# xmas_tree_pcb_A.net
KiCad netlist of a schematic drawn in EAGLE
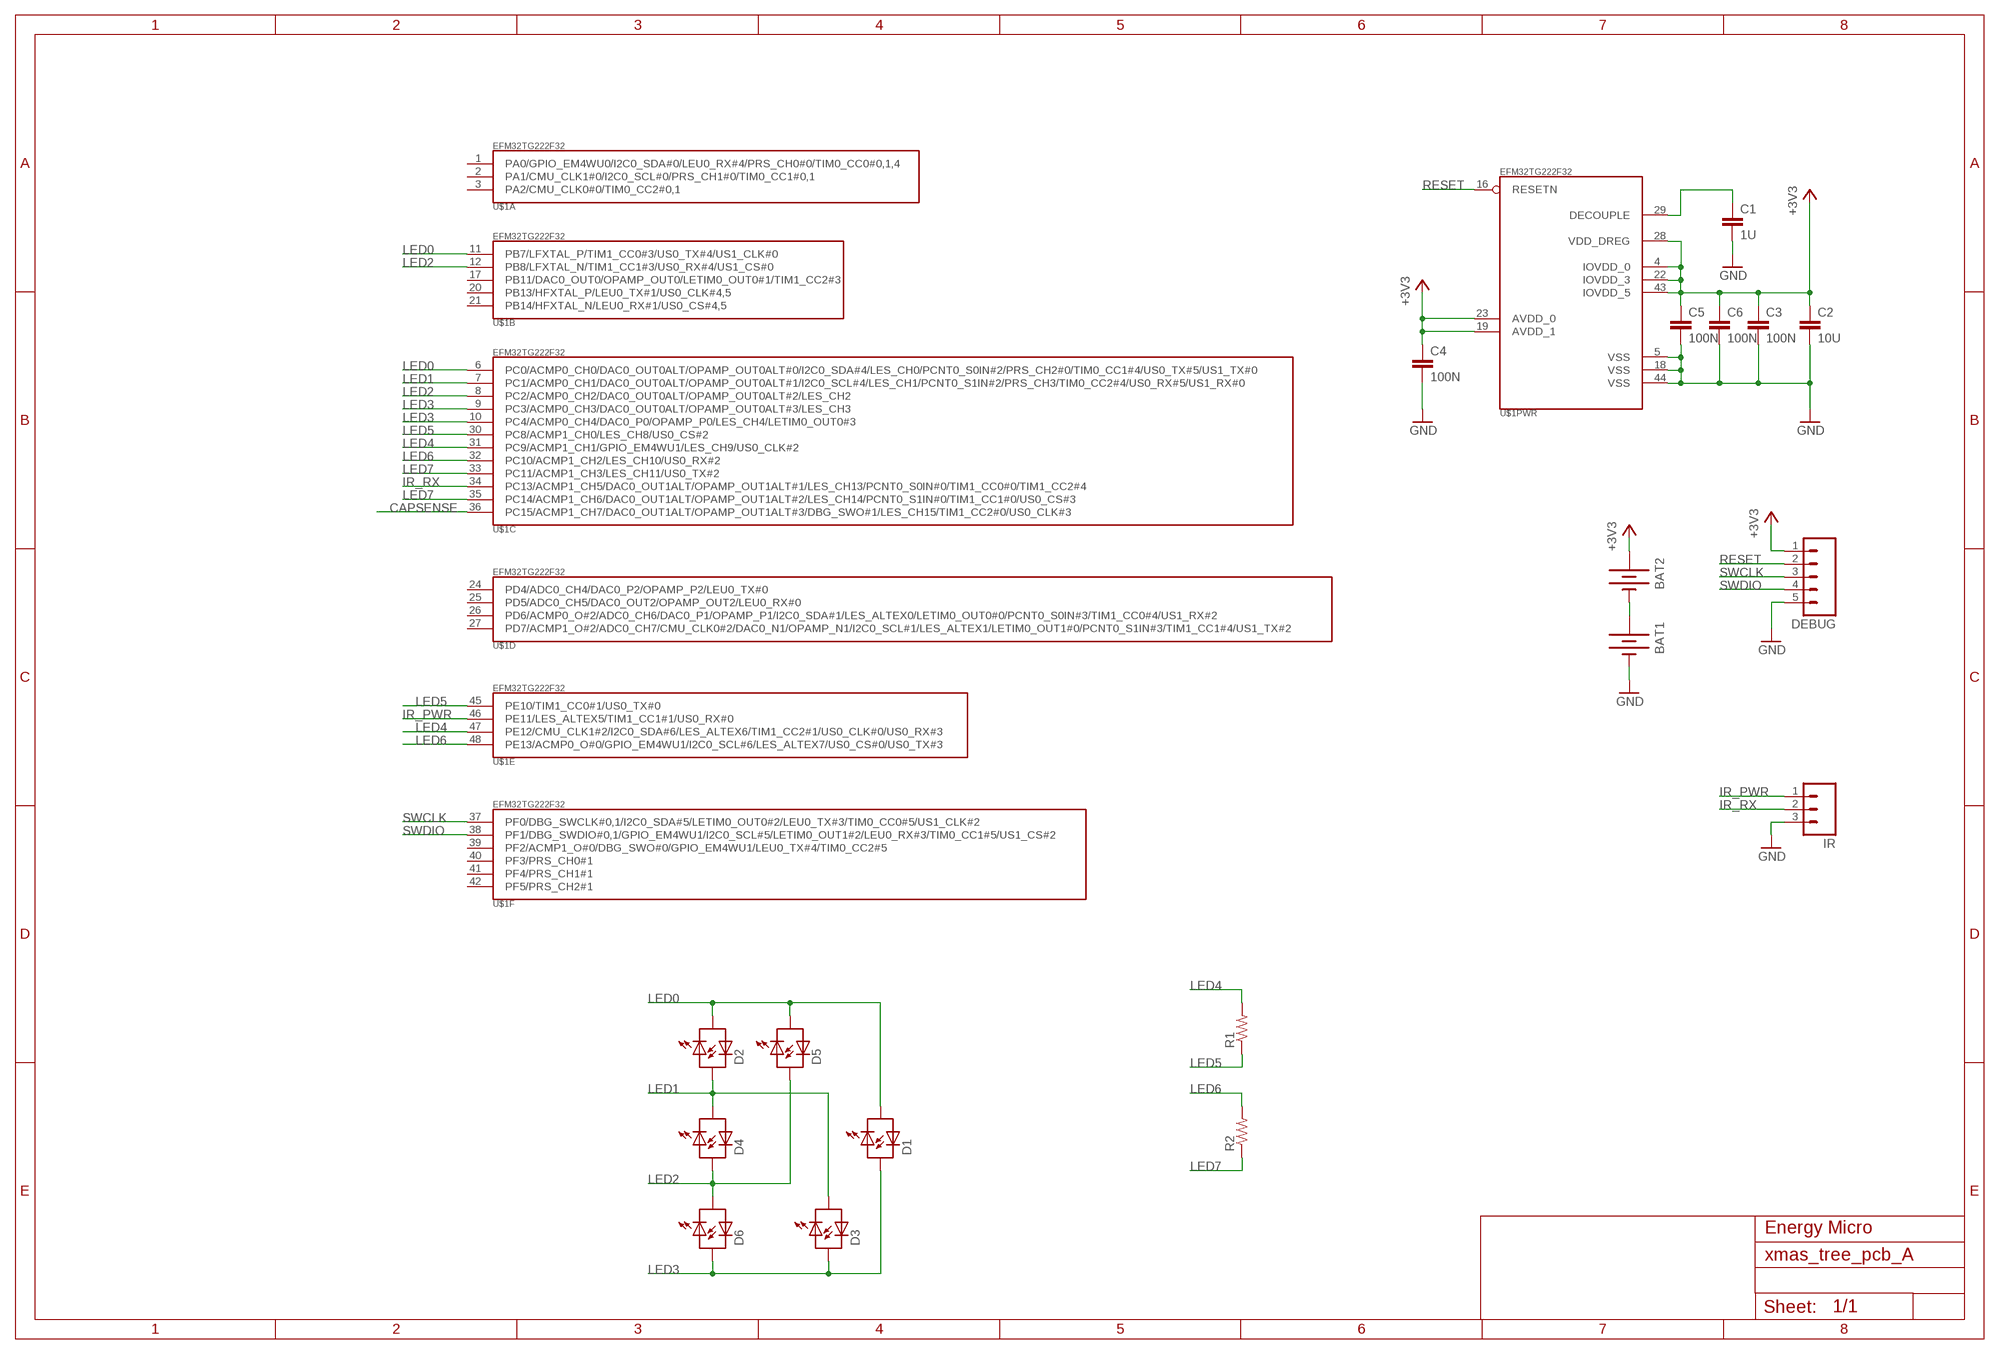
[diagram p0: schematic, sheet 1]

(export (version "E")
  (design (tool "Eeschema 10.0.6"))
  (components
    (comp (ref "BAT1")
      (value "BATTERYAAA")
      (footprint "eagle-import:BATTERY-AAA")
      (libsource (lib "eagle-import") (part "BATTERYAAA"))
    )
    (comp (ref "BAT2")
      (value "BATTERYAAA")
      (footprint "eagle-import:BATTERY-AAA")
      (libsource (lib "eagle-import") (part "BATTERYAAA"))
    )
    (comp (ref "C1")
      (value "1U")
      (footprint "eagle-import:C0603")
      (libsource (lib "eagle-import") (part "C-EUC0603"))
    )
    (comp (ref "C2")
      (value "10U")
      (footprint "eagle-import:C0603")
      (libsource (lib "eagle-import") (part "C-EUC0603"))
    )
    (comp (ref "C3")
      (value "100N")
      (footprint "eagle-import:C0603")
      (libsource (lib "eagle-import") (part "C-EUC0603"))
    )
    (comp (ref "C4")
      (value "100N")
      (footprint "eagle-import:C0603")
      (libsource (lib "eagle-import") (part "C-EUC0603"))
    )
    (comp (ref "C5")
      (value "100N")
      (footprint "eagle-import:C0603")
      (libsource (lib "eagle-import") (part "C-EUC0603"))
    )
    (comp (ref "C6")
      (value "100N")
      (footprint "eagle-import:C0603")
      (libsource (lib "eagle-import") (part "C-EUC0603"))
    )
    (comp (ref "D1")
      (value "LED_BI_COLOR")
      (footprint "eagle-import:LED3MM")
      (libsource (lib "eagle-import") (part "LED_BI_COLOR"))
    )
    (comp (ref "D2")
      (value "LED_BI_COLOR")
      (footprint "eagle-import:LED3MM")
      (libsource (lib "eagle-import") (part "LED_BI_COLOR"))
    )
    (comp (ref "D3")
      (value "LED_BI_COLOR")
      (footprint "eagle-import:LED3MM")
      (libsource (lib "eagle-import") (part "LED_BI_COLOR"))
    )
    (comp (ref "D4")
      (value "LED_BI_COLOR")
      (footprint "eagle-import:LED3MM")
      (libsource (lib "eagle-import") (part "LED_BI_COLOR"))
    )
    (comp (ref "D5")
      (value "LED_BI_COLOR")
      (footprint "eagle-import:LED3MM")
      (libsource (lib "eagle-import") (part "LED_BI_COLOR"))
    )
    (comp (ref "D6")
      (value "LED_BI_COLOR")
      (footprint "eagle-import:LED3MM")
      (libsource (lib "eagle-import") (part "LED_BI_COLOR"))
    )
    (comp (ref "DEBUG")
      (value "M05LOCK")
      (footprint "eagle-import:1X05_LOCK")
      (libsource (lib "eagle-import") (part "M05LOCK"))
    )
    (comp (ref "IR")
      (value "M03LOCK")
      (footprint "eagle-import:1X03_LOCK")
      (libsource (lib "eagle-import") (part "M03LOCK"))
    )
    (comp (ref "R1")
      (value "RESISTOR1206")
      (footprint "eagle-import:1206")
      (libsource (lib "eagle-import") (part "RESISTOR1206"))
    )
    (comp (ref "R2")
      (value "RESISTOR1206")
      (footprint "eagle-import:1206")
      (libsource (lib "eagle-import") (part "RESISTOR1206"))
    )
    (comp (ref "U$1")
      (value "EFM32TG222F32")
      (footprint "eagle-import:QFP48")
      (libsource (lib "eagle-import") (part "EFM32TG222F32"))
    )
  )
  (nets
    (net (code "1") (name "+3V3") (class "Default")
      (node (ref "BAT2") (pin "PWR@1") (pinfunction "+_PWR@1") (pintype "power_in"))
      (node (ref "C2") (pin "1") (pinfunction "1_1") (pintype "passive"))
      (node (ref "C3") (pin "1") (pinfunction "1_1") (pintype "passive"))
      (node (ref "C4") (pin "1") (pinfunction "1_1") (pintype "passive"))
      (node (ref "C5") (pin "1") (pinfunction "1_1") (pintype "passive"))
      (node (ref "C6") (pin "1") (pinfunction "1_1") (pintype "passive"))
      (node (ref "DEBUG") (pin "1") (pinfunction "1_1") (pintype "passive"))
      (node (ref "U$1") (pin "19") (pinfunction "AVDD_1_19") (pintype "power_in"))
      (node (ref "U$1") (pin "22") (pinfunction "IOVDD_3_22") (pintype "power_in"))
      (node (ref "U$1") (pin "23") (pinfunction "AVDD_0_23") (pintype "power_in"))
      (node (ref "U$1") (pin "28") (pinfunction "VDD_DREG_28") (pintype "power_in"))
      (node (ref "U$1") (pin "4") (pinfunction "IOVDD_0_4") (pintype "power_in"))
      (node (ref "U$1") (pin "43") (pinfunction "IOVDD_5_43") (pintype "power_in"))
    )
    (net (code "2") (name "/CAPSENSE") (class "Default")
      (node (ref "U$1") (pin "36") (pinfunction "PC15/ACMP1_CH7/DAC0_OUT1ALT/OPAMP_OUT1ALT#3/DBG_SWO#1/LES_CH15/TIM1_CC2#0/US0_CLK#3_36") (pintype "bidirectional"))
    )
    (net (code "3") (name "/IR_PWR") (class "Default")
      (node (ref "IR") (pin "1") (pinfunction "1_1") (pintype "passive"))
      (node (ref "U$1") (pin "46") (pinfunction "PE11/LES_ALTEX5/TIM1_CC1#1/US0_RX#0_46") (pintype "bidirectional"))
    )
    (net (code "4") (name "/IR_RX") (class "Default")
      (node (ref "IR") (pin "2") (pinfunction "2_2") (pintype "passive"))
      (node (ref "U$1") (pin "34") (pinfunction "PC13/ACMP1_CH5/DAC0_OUT1ALT/OPAMP_OUT1ALT#1/LES_CH13/PCNT0_S0IN#0/TIM1_CC0#0/TIM1_CC2#4_34") (pintype "bidirectional"))
    )
    (net (code "5") (name "/LED0") (class "Default")
      (node (ref "D1") (pin "K") (pinfunction "C1_K") (pintype "passive"))
      (node (ref "D2") (pin "K") (pinfunction "C1_K") (pintype "passive"))
      (node (ref "D5") (pin "K") (pinfunction "C1_K") (pintype "passive"))
      (node (ref "U$1") (pin "11") (pinfunction "PB7/LFXTAL_P/TIM1_CC0#3/US0_TX#4/US1_CLK#0_11") (pintype "bidirectional"))
      (node (ref "U$1") (pin "6") (pinfunction "PC0/ACMP0_CH0/DAC0_OUT0ALT/OPAMP_OUT0ALT#0/I2C0_SDA#4/LES_CH0/PCNT0_S0IN#2/PRS_CH2#0/TIM0_CC1#4/US0_TX#5/US1_TX#0_6") (pintype "bidirectional"))
    )
    (net (code "6") (name "/LED1") (class "Default")
      (node (ref "D2") (pin "A") (pinfunction "A1_A") (pintype "passive"))
      (node (ref "D3") (pin "K") (pinfunction "C1_K") (pintype "passive"))
      (node (ref "D4") (pin "K") (pinfunction "C1_K") (pintype "passive"))
      (node (ref "U$1") (pin "7") (pinfunction "PC1/ACMP0_CH1/DAC0_OUT0ALT/OPAMP_OUT0ALT#1/I2C0_SCL#4/LES_CH1/PCNT0_S1IN#2/PRS_CH3/TIM0_CC2#4/US0_RX#5/US1_RX#0_7") (pintype "bidirectional"))
    )
    (net (code "7") (name "/LED2") (class "Default")
      (node (ref "D4") (pin "A") (pinfunction "A1_A") (pintype "passive"))
      (node (ref "D5") (pin "A") (pinfunction "A1_A") (pintype "passive"))
      (node (ref "D6") (pin "K") (pinfunction "C1_K") (pintype "passive"))
      (node (ref "U$1") (pin "12") (pinfunction "PB8/LFXTAL_N/TIM1_CC1#3/US0_RX#4/US1_CS#0_12") (pintype "bidirectional"))
      (node (ref "U$1") (pin "8") (pinfunction "PC2/ACMP0_CH2/DAC0_OUT0ALT/OPAMP_OUT0ALT#2/LES_CH2_8") (pintype "bidirectional"))
    )
    (net (code "8") (name "/LED3") (class "Default")
      (node (ref "D1") (pin "A") (pinfunction "A1_A") (pintype "passive"))
      (node (ref "D3") (pin "A") (pinfunction "A1_A") (pintype "passive"))
      (node (ref "D6") (pin "A") (pinfunction "A1_A") (pintype "passive"))
      (node (ref "U$1") (pin "10") (pinfunction "PC4/ACMP0_CH4/DAC0_P0/OPAMP_P0/LES_CH4/LETIM0_OUT0#3_10") (pintype "bidirectional"))
      (node (ref "U$1") (pin "9") (pinfunction "PC3/ACMP0_CH3/DAC0_OUT0ALT/OPAMP_OUT0ALT#3/LES_CH3_9") (pintype "bidirectional"))
    )
    (net (code "9") (name "/LED4") (class "Default")
      (node (ref "R1") (pin "2") (pinfunction "2_2") (pintype "passive"))
      (node (ref "U$1") (pin "31") (pinfunction "PC9/ACMP1_CH1/GPIO_EM4WU1/LES_CH9/US0_CLK#2_31") (pintype "bidirectional"))
      (node (ref "U$1") (pin "47") (pinfunction "PE12/CMU_CLK1#2/I2C0_SDA#6/LES_ALTEX6/TIM1_CC2#1/US0_CLK#0/US0_RX#3_47") (pintype "bidirectional"))
    )
    (net (code "10") (name "/LED5") (class "Default")
      (node (ref "R1") (pin "1") (pinfunction "1_1") (pintype "passive"))
      (node (ref "U$1") (pin "30") (pinfunction "PC8/ACMP1_CH0/LES_CH8/US0_CS#2_30") (pintype "bidirectional"))
      (node (ref "U$1") (pin "45") (pinfunction "PE10/TIM1_CC0#1/US0_TX#0_45") (pintype "bidirectional"))
    )
    (net (code "11") (name "/LED6") (class "Default")
      (node (ref "R2") (pin "2") (pinfunction "2_2") (pintype "passive"))
      (node (ref "U$1") (pin "32") (pinfunction "PC10/ACMP1_CH2/LES_CH10/US0_RX#2_32") (pintype "bidirectional"))
      (node (ref "U$1") (pin "48") (pinfunction "PE13/ACMP0_O#0/GPIO_EM4WU1/I2C0_SCL#6/LES_ALTEX7/US0_CS#0/US0_TX#3_48") (pintype "bidirectional"))
    )
    (net (code "12") (name "/LED7") (class "Default")
      (node (ref "R2") (pin "1") (pinfunction "1_1") (pintype "passive"))
      (node (ref "U$1") (pin "33") (pinfunction "PC11/ACMP1_CH3/LES_CH11/US0_TX#2_33") (pintype "bidirectional"))
      (node (ref "U$1") (pin "35") (pinfunction "PC14/ACMP1_CH6/DAC0_OUT1ALT/OPAMP_OUT1ALT#2/LES_CH14/PCNT0_S1IN#0/TIM1_CC1#0/US0_CS#3_35") (pintype "bidirectional"))
    )
    (net (code "13") (name "/RESET") (class "Default")
      (node (ref "DEBUG") (pin "2") (pinfunction "2_2") (pintype "passive"))
      (node (ref "U$1") (pin "16") (pinfunction "RESETN_16") (pintype "passive"))
    )
    (net (code "14") (name "/SWCLK") (class "Default")
      (node (ref "DEBUG") (pin "3") (pinfunction "3_3") (pintype "passive"))
      (node (ref "U$1") (pin "37") (pinfunction "PF0/DBG_SWCLK#0,1/I2C0_SDA#5/LETIM0_OUT0#2/LEU0_TX#3/TIM0_CC0#5/US1_CLK#2_37") (pintype "bidirectional"))
    )
    (net (code "15") (name "/SWDIO") (class "Default")
      (node (ref "DEBUG") (pin "4") (pinfunction "4_4") (pintype "passive"))
      (node (ref "U$1") (pin "38") (pinfunction "PF1/DBG_SWDIO#0,1/GPIO_EM4WU1/I2C0_SCL#5/LETIM0_OUT1#2/LEU0_RX#3/TIM0_CC1#5/US1_CS#2_38") (pintype "bidirectional"))
    )
    (net (code "16") (name "GND") (class "Default")
      (node (ref "BAT1") (pin "GND@1") (pinfunction "-_GND@1") (pintype "power_in"))
      (node (ref "C1") (pin "2") (pinfunction "2_2") (pintype "passive"))
      (node (ref "C2") (pin "2") (pinfunction "2_2") (pintype "passive"))
      (node (ref "C3") (pin "2") (pinfunction "2_2") (pintype "passive"))
      (node (ref "C4") (pin "2") (pinfunction "2_2") (pintype "passive"))
      (node (ref "C5") (pin "2") (pinfunction "2_2") (pintype "passive"))
      (node (ref "C6") (pin "2") (pinfunction "2_2") (pintype "passive"))
      (node (ref "DEBUG") (pin "5") (pinfunction "5_5") (pintype "passive"))
      (node (ref "IR") (pin "3") (pinfunction "3_3") (pintype "passive"))
      (node (ref "U$1") (pin "18") (pinfunction "VSS_18") (pintype "power_in"))
      (node (ref "U$1") (pin "44") (pinfunction "VSS_44") (pintype "power_in"))
      (node (ref "U$1") (pin "5") (pinfunction "VSS_5") (pintype "power_in"))
    )
    (net (code "17") (name "Net-(BAT1-+)") (class "Default")
      (node (ref "BAT1") (pin "PWR@1") (pinfunction "+_PWR@1") (pintype "power_in"))
      (node (ref "BAT2") (pin "GND@1") (pinfunction "-_GND@1") (pintype "power_in"))
    )
    (net (code "18") (name "Net-(U$1G-DECOUPLE)") (class "Default")
      (node (ref "C1") (pin "1") (pinfunction "1_1") (pintype "passive"))
      (node (ref "U$1") (pin "29") (pinfunction "DECOUPLE_29") (pintype "power_in"))
    )
    (net (code "19") (name "unconnected-(U$1A-PA0{slash}GPIO_EM4WU0{slash}I2C0_SDA#0{slash}LEU0_RX#4{slash}PRS_CH0#0{slash}TIM0_CC0#0,1,4-Pad1)") (class "Default")
      (node (ref "U$1") (pin "1") (pinfunction "PA0/GPIO_EM4WU0/I2C0_SDA#0/LEU0_RX#4/PRS_CH0#0/TIM0_CC0#0,1,4_1") (pintype "bidirectional"))
    )
    (net (code "20") (name "unconnected-(U$1A-PA1{slash}CMU_CLK1#0{slash}I2C0_SCL#0{slash}PRS_CH1#0{slash}TIM0_CC1#0,1-Pad2)") (class "Default")
      (node (ref "U$1") (pin "2") (pinfunction "PA1/CMU_CLK1#0/I2C0_SCL#0/PRS_CH1#0/TIM0_CC1#0,1_2") (pintype "bidirectional"))
    )
    (net (code "21") (name "unconnected-(U$1A-PA2{slash}CMU_CLK0#0{slash}TIM0_CC2#0,1-Pad3)") (class "Default")
      (node (ref "U$1") (pin "3") (pinfunction "PA2/CMU_CLK0#0/TIM0_CC2#0,1_3") (pintype "bidirectional"))
    )
    (net (code "22") (name "unconnected-(U$1B-PB11{slash}DAC0_OUT0{slash}OPAMP_OUT0{slash}LETIM0_OUT0#1{slash}TIM1_CC2#3-Pad17)") (class "Default")
      (node (ref "U$1") (pin "17") (pinfunction "PB11/DAC0_OUT0/OPAMP_OUT0/LETIM0_OUT0#1/TIM1_CC2#3_17") (pintype "bidirectional"))
    )
    (net (code "23") (name "unconnected-(U$1B-PB13{slash}HFXTAL_P{slash}LEU0_TX#1{slash}US0_CLK#4,5-Pad20)") (class "Default")
      (node (ref "U$1") (pin "20") (pinfunction "PB13/HFXTAL_P/LEU0_TX#1/US0_CLK#4,5_20") (pintype "bidirectional"))
    )
    (net (code "24") (name "unconnected-(U$1B-PB14{slash}HFXTAL_N{slash}LEU0_RX#1{slash}US0_CS#4,5-Pad21)") (class "Default")
      (node (ref "U$1") (pin "21") (pinfunction "PB14/HFXTAL_N/LEU0_RX#1/US0_CS#4,5_21") (pintype "bidirectional"))
    )
    (net (code "25") (name "unconnected-(U$1D-PD4{slash}ADC0_CH4{slash}DAC0_P2{slash}OPAMP_P2{slash}LEU0_TX#0-Pad24)") (class "Default")
      (node (ref "U$1") (pin "24") (pinfunction "PD4/ADC0_CH4/DAC0_P2/OPAMP_P2/LEU0_TX#0_24") (pintype "bidirectional"))
    )
    (net (code "26") (name "unconnected-(U$1D-PD5{slash}ADC0_CH5{slash}DAC0_OUT2{slash}OPAMP_OUT2{slash}LEU0_RX#0-Pad25)") (class "Default")
      (node (ref "U$1") (pin "25") (pinfunction "PD5/ADC0_CH5/DAC0_OUT2/OPAMP_OUT2/LEU0_RX#0_25") (pintype "bidirectional"))
    )
    (net (code "27") (name "unconnected-(U$1D-PD6{slash}ACMP0_O#2{slash}ADC0_CH6{slash}DAC0_P1{slash}OPAMP_P1{slash}I2C0_SDA#1{slash}LES_ALTEX0{slash}LETIM0_OUT0#0{slash}PCNT0_S0IN#3{slash}TIM1_CC0#4{slash}US1_RX#2-Pad26)") (class "Default")
      (node (ref "U$1") (pin "26") (pinfunction "PD6/ACMP0_O#2/ADC0_CH6/DAC0_P1/OPAMP_P1/I2C0_SDA#1/LES_ALTEX0/LETIM0_OUT0#0/PCNT0_S0IN#3/TIM1_CC0#4/US1_RX#2_26") (pintype "bidirectional"))
    )
    (net (code "28") (name "unconnected-(U$1D-PD7{slash}ACMP1_O#2{slash}ADC0_CH7{slash}CMU_CLK0#2{slash}DAC0_N1{slash}OPAMP_N1{slash}I2C0_SCL#1{slash}LES_ALTEX1{slash}LETIM0_OUT1#0{slash}PCNT0_S1IN#3{slash}TIM1_CC1#4{slash}US1_TX#2-Pad27)") (class "Default")
      (node (ref "U$1") (pin "27") (pinfunction "PD7/ACMP1_O#2/ADC0_CH7/CMU_CLK0#2/DAC0_N1/OPAMP_N1/I2C0_SCL#1/LES_ALTEX1/LETIM0_OUT1#0/PCNT0_S1IN#3/TIM1_CC1#4/US1_TX#2_27") (pintype "bidirectional"))
    )
    (net (code "29") (name "unconnected-(U$1F-PF2{slash}ACMP1_O#0{slash}DBG_SWO#0{slash}GPIO_EM4WU1{slash}LEU0_TX#4{slash}TIM0_CC2#5-Pad39)") (class "Default")
      (node (ref "U$1") (pin "39") (pinfunction "PF2/ACMP1_O#0/DBG_SWO#0/GPIO_EM4WU1/LEU0_TX#4/TIM0_CC2#5_39") (pintype "bidirectional"))
    )
    (net (code "30") (name "unconnected-(U$1F-PF3{slash}PRS_CH0#1-Pad40)") (class "Default")
      (node (ref "U$1") (pin "40") (pinfunction "PF3/PRS_CH0#1_40") (pintype "bidirectional"))
    )
    (net (code "31") (name "unconnected-(U$1F-PF4{slash}PRS_CH1#1-Pad41)") (class "Default")
      (node (ref "U$1") (pin "41") (pinfunction "PF4/PRS_CH1#1_41") (pintype "bidirectional"))
    )
    (net (code "32") (name "unconnected-(U$1F-PF5{slash}PRS_CH2#1-Pad42)") (class "Default")
      (node (ref "U$1") (pin "42") (pinfunction "PF5/PRS_CH2#1_42") (pintype "bidirectional"))
    )
  )
)
